# Schmatic_ReallyARobot_AD_PIR_Module_V1_0.net
KiCad netlist of a schematic drawn in Altium Designer
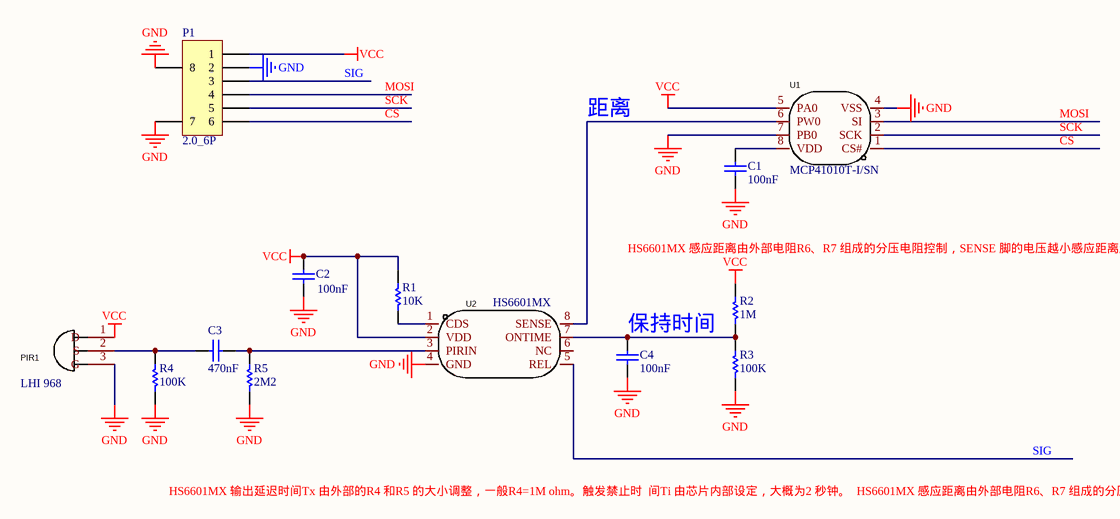
[diagram p0: Schmatic_ReallyARobot_AD PIR Module V1.0.SchDoc]

(export (version "E")
  (design (tool "Eeschema 10.0.6"))
  (components
    (comp (ref "C1")
      (value "100nF")
      (footprint "0805C")
      (description "Capacitor")
      (fields (field (name "PUBLISHER") "Altium Limited"))
      (libsource (lib "Miscellaneous Devices") (part "Cap"))
    )
    (comp (ref "C2")
      (value "100nF")
      (footprint "0603C")
      (description "Capacitor")
      (fields (field (name "PUBLISHER") "Altium Limited"))
      (libsource (lib "*") (part "Cap"))
    )
    (comp (ref "C3")
      (value "470nF")
      (footprint "0603C")
      (description "Capacitor")
      (fields (field (name "PUBLISHER") "Altium Limited"))
      (libsource (lib "*") (part "Cap"))
    )
    (comp (ref "C4")
      (value "100nF")
      (footprint "0805C")
      (description "Capacitor")
      (fields (field (name "PUBLISHER") "Altium Limited"))
      (libsource (lib "Miscellaneous Devices") (part "Cap"))
    )
    (comp (ref "P1")
      (value "2.0_6P")
      (footprint "HDR1X6")
      (description "Header, 6-Pin")
      (fields (field (name "PUBLISHER") "Altium Limited"))
      (libsource (lib "Miscellaneous Connectors") (part "Header 6"))
    )
    (comp (ref "PIR1")
      (value "LHI 968")
      (footprint "TO-5-3_L8.2-W8.2")
      (fields (field (name "MANUFACTURER PART") "D203S"))
      (libsource (lib "altium-import") (part "root_0_mirrored_D203S_"))
    )
    (comp (ref "R1")
      (value "10K")
      (footprint "0805R")
      (description "Resistor")
      (fields (field (name "PUBLISHER") "Altium Limited"))
      (libsource (lib "Miscellaneous Devices") (part "Res1"))
    )
    (comp (ref "R2")
      (value "1M")
      (footprint "0805R")
      (description "Resistor")
      (fields (field (name "PUBLISHER") "Altium Limited"))
      (libsource (lib "Miscellaneous Devices") (part "Res1"))
    )
    (comp (ref "R3")
      (value "100K")
      (footprint "0805R")
      (description "Resistor")
      (fields (field (name "PUBLISHER") "Altium Limited"))
      (libsource (lib "Miscellaneous Devices") (part "Res1"))
    )
    (comp (ref "R4")
      (value "100K")
      (footprint "0805R")
      (description "Resistor")
      (fields (field (name "PUBLISHER") "Altium Limited"))
      (libsource (lib "Miscellaneous Devices") (part "Res1"))
    )
    (comp (ref "R5")
      (value "2M2")
      (footprint "0805R")
      (description "Resistor")
      (fields (field (name "PUBLISHER") "Altium Limited"))
      (libsource (lib "Miscellaneous Devices") (part "Res1"))
    )
    (comp (ref "U1")
      (value "MCP41010T-I/SN")
      (footprint "SO-8")
      (libsource (lib "altium-import") (part "root_2_MCP41010T-I/SN_"))
    )
    (comp (ref "U2")
      (value "HS6601MX")
      (footprint "SOP-8_L4.9-W3.9-P1.27-LS6.0-BL")
      (libsource (lib "altium-import") (part "root_0_HS6601MX_"))
    )
  )
  (nets
    (net (code "1") (name "/CS") (class "Default")
      (node (ref "P1") (pin "6") (pinfunction "6_6") (pintype "passive"))
      (node (ref "U1") (pin "1") (pinfunction "CS#_1") (pintype "passive"))
    )
    (net (code "4") (name "/MOSI") (class "Default")
      (node (ref "P1") (pin "4") (pinfunction "4_4") (pintype "passive"))
      (node (ref "U1") (pin "3") (pinfunction "SI_3") (pintype "passive"))
    )
    (net (code "5") (name "/SCK") (class "Default")
      (node (ref "P1") (pin "5") (pinfunction "5_5") (pintype "passive"))
      (node (ref "U1") (pin "2") (pinfunction "SCK_2") (pintype "passive"))
    )
    (net (code "6") (name "/SIG") (class "Default")
      (node (ref "P1") (pin "3") (pinfunction "3_3") (pintype "passive"))
      (node (ref "U2") (pin "5") (pinfunction "REL_5") (pintype "passive"))
    )
    (net (code "7") (name "GND") (class "Default")
      (node (ref "C1") (pin "1") (pinfunction "1_1") (pintype "passive"))
      (node (ref "C2") (pin "1") (pinfunction "1_1") (pintype "passive"))
      (node (ref "C4") (pin "1") (pinfunction "1_1") (pintype "passive"))
      (node (ref "P1") (pin "2") (pinfunction "2_2") (pintype "passive"))
      (node (ref "P1") (pin "7") (pinfunction "7_7") (pintype "passive"))
      (node (ref "P1") (pin "8") (pinfunction "8_8") (pintype "passive"))
      (node (ref "PIR1") (pin "3") (pinfunction "G_3") (pintype "passive"))
      (node (ref "R3") (pin "2") (pinfunction "2_2") (pintype "passive"))
      (node (ref "R4") (pin "2") (pinfunction "2_2") (pintype "passive"))
      (node (ref "R5") (pin "2") (pinfunction "2_2") (pintype "passive"))
      (node (ref "U1") (pin "4") (pinfunction "VSS_4") (pintype "passive"))
      (node (ref "U1") (pin "7") (pinfunction "PB0_7") (pintype "passive"))
      (node (ref "U2") (pin "4") (pinfunction "GND_4") (pintype "passive"))
    )
    (net (code "8") (name "Net-(PIR1-S)") (class "Default")
      (node (ref "C3") (pin "2") (pinfunction "2_2") (pintype "passive"))
      (node (ref "PIR1") (pin "2") (pinfunction "S_2") (pintype "passive"))
      (node (ref "R4") (pin "1") (pinfunction "1_1") (pintype "passive"))
    )
    (net (code "9") (name "Net-(U1-PW0)") (class "Default")
      (node (ref "U1") (pin "6") (pinfunction "PW0_6") (pintype "passive"))
      (node (ref "U2") (pin "8") (pinfunction "SENSE_8") (pintype "passive"))
    )
    (net (code "10") (name "Net-(U1-VDD)") (class "Default")
      (node (ref "C1") (pin "2") (pinfunction "2_2") (pintype "passive"))
      (node (ref "U1") (pin "8") (pinfunction "VDD_8") (pintype "passive"))
    )
    (net (code "11") (name "Net-(U2-CDS)") (class "Default")
      (node (ref "R1") (pin "2") (pinfunction "2_2") (pintype "passive"))
      (node (ref "U2") (pin "1") (pinfunction "CDS_1") (pintype "passive"))
    )
    (net (code "12") (name "Net-(U2-ONTIME)") (class "Default")
      (node (ref "C4") (pin "2") (pinfunction "2_2") (pintype "passive"))
      (node (ref "R2") (pin "2") (pinfunction "2_2") (pintype "passive"))
      (node (ref "R3") (pin "1") (pinfunction "1_1") (pintype "passive"))
      (node (ref "U2") (pin "7") (pinfunction "ONTIME_7") (pintype "passive"))
    )
    (net (code "13") (name "Net-(U2-PIRIN)") (class "Default")
      (node (ref "C3") (pin "1") (pinfunction "1_1") (pintype "passive"))
      (node (ref "R5") (pin "1") (pinfunction "1_1") (pintype "passive"))
      (node (ref "U2") (pin "3") (pinfunction "PIRIN_3") (pintype "passive"))
    )
    (net (code "14") (name "VCC") (class "Default")
      (node (ref "C2") (pin "2") (pinfunction "2_2") (pintype "passive"))
      (node (ref "P1") (pin "1") (pinfunction "1_1") (pintype "passive"))
      (node (ref "PIR1") (pin "1") (pinfunction "D_1") (pintype "passive"))
      (node (ref "R1") (pin "1") (pinfunction "1_1") (pintype "passive"))
      (node (ref "R2") (pin "1") (pinfunction "1_1") (pintype "passive"))
      (node (ref "U1") (pin "5") (pinfunction "PA0_5") (pintype "passive"))
      (node (ref "U2") (pin "2") (pinfunction "VDD_2") (pintype "passive"))
    )
    (net (code "15") (name "unconnected-(U2-NC-Pad6)") (class "Default")
      (node (ref "U2") (pin "6") (pinfunction "NC_6") (pintype "passive"))
    )
  )
)
